# FP_connectors.net
KiCad netlist of a schematic drawn in Altium Designer
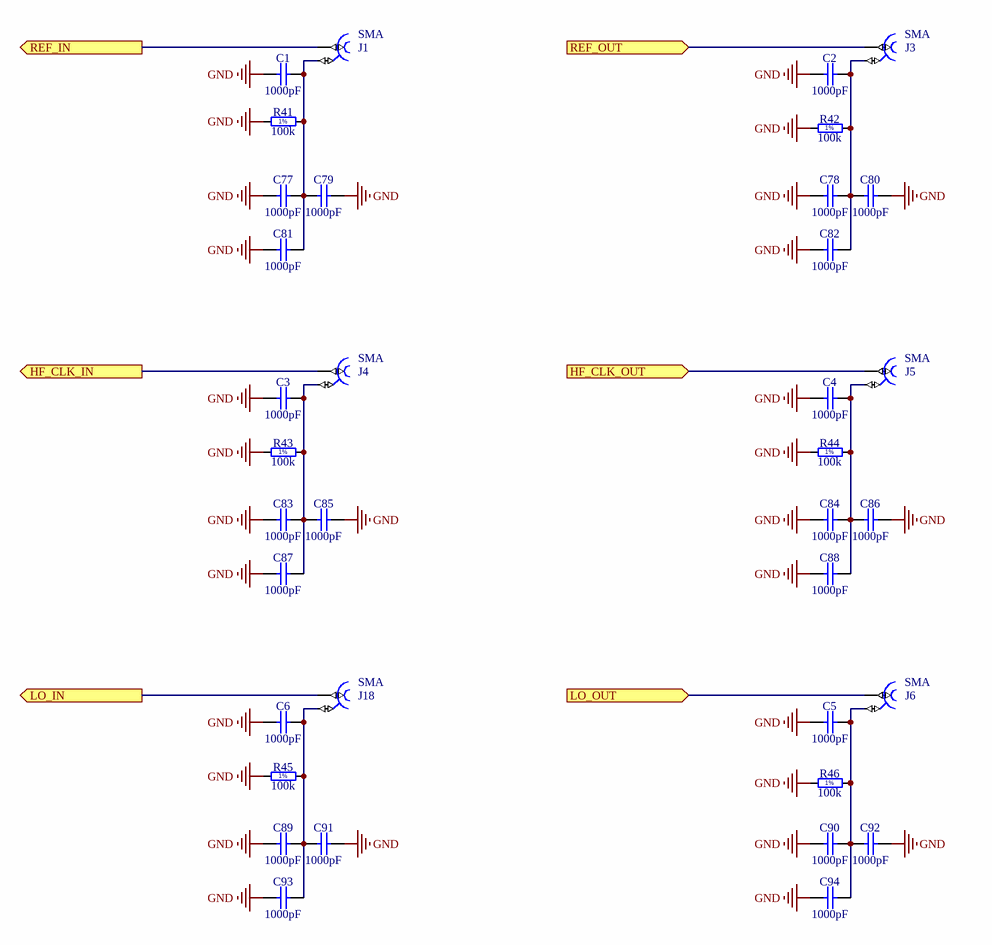
[diagram p0: FP_connectors.SchDoc]

(export (version "E")
  (design (tool "Eeschema 10.0.6"))
  (components
    (comp (ref "C1")
      (value "1000pF")
      (footprint "CAPC1005X55N")
      (description "Non-polarised capacitor")
      (fields
        (field (name "PART NUMBER") "CC0402_1000PF_50V_5%_C0G")
        (field (name "VOLTAGE") "50V")
        (field (name "AUTHOR") "CERN DEM JLC")
      )
      (libsource (lib "Capacitors") (part "Capacitor - non polarized"))
    )
    (comp (ref "C2")
      (value "1000pF")
      (footprint "CAPC1005X55N")
      (description "Non-polarised capacitor")
      (fields
        (field (name "PART NUMBER") "CC0402_1000PF_50V_5%_C0G")
        (field (name "VOLTAGE") "50V")
        (field (name "AUTHOR") "CERN DEM JLC")
      )
      (libsource (lib "Capacitors") (part "Capacitor - non polarized"))
    )
    (comp (ref "C3")
      (value "1000pF")
      (footprint "CAPC1005X55N")
      (description "Non-polarised capacitor")
      (fields
        (field (name "PART NUMBER") "CC0402_1000PF_50V_5%_C0G")
        (field (name "VOLTAGE") "50V")
        (field (name "AUTHOR") "CERN DEM JLC")
      )
      (libsource (lib "Capacitors") (part "Capacitor - non polarized"))
    )
    (comp (ref "C4")
      (value "1000pF")
      (footprint "CAPC1005X55N")
      (description "Non-polarised capacitor")
      (fields
        (field (name "PART NUMBER") "CC0402_1000PF_50V_5%_C0G")
        (field (name "VOLTAGE") "50V")
        (field (name "AUTHOR") "CERN DEM JLC")
      )
      (libsource (lib "Capacitors") (part "Capacitor - non polarized"))
    )
    (comp (ref "C5")
      (value "1000pF")
      (footprint "CAPC1005X55N")
      (description "Non-polarised capacitor")
      (fields
        (field (name "PART NUMBER") "CC0402_1000PF_50V_5%_C0G")
        (field (name "VOLTAGE") "50V")
        (field (name "AUTHOR") "CERN DEM JLC")
      )
      (libsource (lib "Capacitors") (part "Capacitor - non polarized"))
    )
    (comp (ref "C6")
      (value "1000pF")
      (footprint "CAPC1005X55N")
      (description "Non-polarised capacitor")
      (fields
        (field (name "PART NUMBER") "CC0402_1000PF_50V_5%_C0G")
        (field (name "VOLTAGE") "50V")
        (field (name "AUTHOR") "CERN DEM JLC")
      )
      (libsource (lib "Capacitors") (part "Capacitor - non polarized"))
    )
    (comp (ref "C77")
      (value "1000pF")
      (footprint "CAPC1005X55N")
      (description "Non-polarised capacitor")
      (fields
        (field (name "PART NUMBER") "CC0402_1000PF_50V_5%_C0G")
        (field (name "VOLTAGE") "50V")
        (field (name "AUTHOR") "CERN DEM JLC")
      )
      (libsource (lib "Capacitors") (part "Capacitor - non polarized"))
    )
    (comp (ref "C78")
      (value "1000pF")
      (footprint "CAPC1005X55N")
      (description "Non-polarised capacitor")
      (fields
        (field (name "PART NUMBER") "CC0402_1000PF_50V_5%_C0G")
        (field (name "VOLTAGE") "50V")
        (field (name "AUTHOR") "CERN DEM JLC")
      )
      (libsource (lib "Capacitors") (part "Capacitor - non polarized"))
    )
    (comp (ref "C79")
      (value "1000pF")
      (footprint "CAPC1005X55N")
      (description "Non-polarised capacitor")
      (fields
        (field (name "PART NUMBER") "CC0402_1000PF_50V_5%_C0G")
        (field (name "VOLTAGE") "50V")
        (field (name "AUTHOR") "CERN DEM JLC")
      )
      (libsource (lib "Capacitors") (part "Capacitor - non polarized"))
    )
    (comp (ref "C80")
      (value "1000pF")
      (footprint "CAPC1005X55N")
      (description "Non-polarised capacitor")
      (fields
        (field (name "PART NUMBER") "CC0402_1000PF_50V_5%_C0G")
        (field (name "VOLTAGE") "50V")
        (field (name "AUTHOR") "CERN DEM JLC")
      )
      (libsource (lib "Capacitors") (part "Capacitor - non polarized"))
    )
    (comp (ref "C81")
      (value "1000pF")
      (footprint "CAPC1005X55N")
      (description "Non-polarised capacitor")
      (fields
        (field (name "PART NUMBER") "CC0402_1000PF_50V_5%_C0G")
        (field (name "VOLTAGE") "50V")
        (field (name "AUTHOR") "CERN DEM JLC")
      )
      (libsource (lib "Capacitors") (part "Capacitor - non polarized"))
    )
    (comp (ref "C82")
      (value "1000pF")
      (footprint "CAPC1005X55N")
      (description "Non-polarised capacitor")
      (fields
        (field (name "PART NUMBER") "CC0402_1000PF_50V_5%_C0G")
        (field (name "VOLTAGE") "50V")
        (field (name "AUTHOR") "CERN DEM JLC")
      )
      (libsource (lib "Capacitors") (part "Capacitor - non polarized"))
    )
    (comp (ref "C83")
      (value "1000pF")
      (footprint "CAPC1005X55N")
      (description "Non-polarised capacitor")
      (fields
        (field (name "PART NUMBER") "CC0402_1000PF_50V_5%_C0G")
        (field (name "VOLTAGE") "50V")
        (field (name "AUTHOR") "CERN DEM JLC")
      )
      (libsource (lib "Capacitors") (part "Capacitor - non polarized"))
    )
    (comp (ref "C84")
      (value "1000pF")
      (footprint "CAPC1005X55N")
      (description "Non-polarised capacitor")
      (fields
        (field (name "PART NUMBER") "CC0402_1000PF_50V_5%_C0G")
        (field (name "VOLTAGE") "50V")
        (field (name "AUTHOR") "CERN DEM JLC")
      )
      (libsource (lib "Capacitors") (part "Capacitor - non polarized"))
    )
    (comp (ref "C85")
      (value "1000pF")
      (footprint "CAPC1005X55N")
      (description "Non-polarised capacitor")
      (fields
        (field (name "PART NUMBER") "CC0402_1000PF_50V_5%_C0G")
        (field (name "VOLTAGE") "50V")
        (field (name "AUTHOR") "CERN DEM JLC")
      )
      (libsource (lib "Capacitors") (part "Capacitor - non polarized"))
    )
    (comp (ref "C86")
      (value "1000pF")
      (footprint "CAPC1005X55N")
      (description "Non-polarised capacitor")
      (fields
        (field (name "PART NUMBER") "CC0402_1000PF_50V_5%_C0G")
        (field (name "VOLTAGE") "50V")
        (field (name "AUTHOR") "CERN DEM JLC")
      )
      (libsource (lib "Capacitors") (part "Capacitor - non polarized"))
    )
    (comp (ref "C87")
      (value "1000pF")
      (footprint "CAPC1005X55N")
      (description "Non-polarised capacitor")
      (fields
        (field (name "PART NUMBER") "CC0402_1000PF_50V_5%_C0G")
        (field (name "VOLTAGE") "50V")
        (field (name "AUTHOR") "CERN DEM JLC")
      )
      (libsource (lib "Capacitors") (part "Capacitor - non polarized"))
    )
    (comp (ref "C88")
      (value "1000pF")
      (footprint "CAPC1005X55N")
      (description "Non-polarised capacitor")
      (fields
        (field (name "PART NUMBER") "CC0402_1000PF_50V_5%_C0G")
        (field (name "VOLTAGE") "50V")
        (field (name "AUTHOR") "CERN DEM JLC")
      )
      (libsource (lib "Capacitors") (part "Capacitor - non polarized"))
    )
    (comp (ref "C89")
      (value "1000pF")
      (footprint "CAPC1005X55N")
      (description "Non-polarised capacitor")
      (fields
        (field (name "PART NUMBER") "CC0402_1000PF_50V_5%_C0G")
        (field (name "VOLTAGE") "50V")
        (field (name "AUTHOR") "CERN DEM JLC")
      )
      (libsource (lib "Capacitors") (part "Capacitor - non polarized"))
    )
    (comp (ref "C90")
      (value "1000pF")
      (footprint "CAPC1005X55N")
      (description "Non-polarised capacitor")
      (fields
        (field (name "PART NUMBER") "CC0402_1000PF_50V_5%_C0G")
        (field (name "VOLTAGE") "50V")
        (field (name "AUTHOR") "CERN DEM JLC")
      )
      (libsource (lib "Capacitors") (part "Capacitor - non polarized"))
    )
    (comp (ref "C91")
      (value "1000pF")
      (footprint "CAPC1005X55N")
      (description "Non-polarised capacitor")
      (fields
        (field (name "PART NUMBER") "CC0402_1000PF_50V_5%_C0G")
        (field (name "VOLTAGE") "50V")
        (field (name "AUTHOR") "CERN DEM JLC")
      )
      (libsource (lib "Capacitors") (part "Capacitor - non polarized"))
    )
    (comp (ref "C92")
      (value "1000pF")
      (footprint "CAPC1005X55N")
      (description "Non-polarised capacitor")
      (fields
        (field (name "PART NUMBER") "CC0402_1000PF_50V_5%_C0G")
        (field (name "VOLTAGE") "50V")
        (field (name "AUTHOR") "CERN DEM JLC")
      )
      (libsource (lib "Capacitors") (part "Capacitor - non polarized"))
    )
    (comp (ref "C93")
      (value "1000pF")
      (footprint "CAPC1005X55N")
      (description "Non-polarised capacitor")
      (fields
        (field (name "PART NUMBER") "CC0402_1000PF_50V_5%_C0G")
        (field (name "VOLTAGE") "50V")
        (field (name "AUTHOR") "CERN DEM JLC")
      )
      (libsource (lib "Capacitors") (part "Capacitor - non polarized"))
    )
    (comp (ref "C94")
      (value "1000pF")
      (footprint "CAPC1005X55N")
      (description "Non-polarised capacitor")
      (fields
        (field (name "PART NUMBER") "CC0402_1000PF_50V_5%_C0G")
        (field (name "VOLTAGE") "50V")
        (field (name "AUTHOR") "CERN DEM JLC")
      )
      (libsource (lib "Capacitors") (part "Capacitor - non polarized"))
    )
    (comp (ref "J1")
      (value "SMA")
      (footprint "TELEGARTNER_J01151A0451")
      (fields
        (field (name "PART NUMBER") "TELEGARTNER_J01151A0451")
        (field (name "MANUFACTURER") "TELEGARTNER")
        (field (name "MANUFACTURER PART NUMBER") "J01151A0451")
        (field (name "AUTHOR") "CERN DEM JLC")
      )
      (libsource (lib "Connectors") (part "Coax_1Female_1Shield"))
    )
    (comp (ref "J3")
      (value "SMA")
      (footprint "TELEGARTNER_J01151A0451")
      (fields
        (field (name "PART NUMBER") "TELEGARTNER_J01151A0451")
        (field (name "MANUFACTURER") "TELEGARTNER")
        (field (name "MANUFACTURER PART NUMBER") "J01151A0451")
        (field (name "AUTHOR") "CERN DEM JLC")
      )
      (libsource (lib "Connectors") (part "Coax_1Female_1Shield"))
    )
    (comp (ref "J4")
      (value "SMA")
      (footprint "TELEGARTNER_J01151A0451")
      (fields
        (field (name "PART NUMBER") "TELEGARTNER_J01151A0451")
        (field (name "MANUFACTURER") "TELEGARTNER")
        (field (name "MANUFACTURER PART NUMBER") "J01151A0451")
        (field (name "AUTHOR") "CERN DEM JLC")
      )
      (libsource (lib "Connectors") (part "Coax_1Female_1Shield"))
    )
    (comp (ref "J5")
      (value "SMA")
      (footprint "TELEGARTNER_J01151A0451")
      (fields
        (field (name "PART NUMBER") "TELEGARTNER_J01151A0451")
        (field (name "MANUFACTURER") "TELEGARTNER")
        (field (name "MANUFACTURER PART NUMBER") "J01151A0451")
        (field (name "AUTHOR") "CERN DEM JLC")
      )
      (libsource (lib "Connectors") (part "Coax_1Female_1Shield"))
    )
    (comp (ref "J6")
      (value "SMA")
      (footprint "TELEGARTNER_J01151A0451")
      (fields
        (field (name "PART NUMBER") "TELEGARTNER_J01151A0451")
        (field (name "MANUFACTURER") "TELEGARTNER")
        (field (name "MANUFACTURER PART NUMBER") "J01151A0451")
        (field (name "AUTHOR") "CERN DEM JLC")
      )
      (libsource (lib "Connectors") (part "Coax_1Female_1Shield"))
    )
    (comp (ref "J18")
      (value "SMA")
      (footprint "TELEGARTNER_J01151A0451")
      (fields
        (field (name "PART NUMBER") "TELEGARTNER_J01151A0451")
        (field (name "MANUFACTURER") "TELEGARTNER")
        (field (name "MANUFACTURER PART NUMBER") "J01151A0451")
        (field (name "AUTHOR") "CERN DEM JLC")
      )
      (libsource (lib "Connectors") (part "Coax_1Female_1Shield"))
    )
    (comp (ref "R41")
      (value "100k")
      (footprint "RESC1005X40N")
      (description "Resistor - 1%")
      (fields
        (field (name "PART NUMBER") "R0402_100k_1%_0.0625W_100PPM")
        (field (name "POWER") "0.0625W")
        (field (name "AUTHOR") "CERN DEM JLC")
      )
      (libsource (lib "Resistors") (part "Resistor - 1%"))
    )
    (comp (ref "R42")
      (value "100k")
      (footprint "RESC1005X40N")
      (description "Resistor - 1%")
      (fields
        (field (name "PART NUMBER") "R0402_100k_1%_0.0625W_100PPM")
        (field (name "POWER") "0.0625W")
        (field (name "AUTHOR") "CERN DEM JLC")
      )
      (libsource (lib "Resistors") (part "Resistor - 1%"))
    )
    (comp (ref "R43")
      (value "100k")
      (footprint "RESC1005X40N")
      (description "Resistor - 1%")
      (fields
        (field (name "PART NUMBER") "R0402_100k_1%_0.0625W_100PPM")
        (field (name "POWER") "0.0625W")
        (field (name "AUTHOR") "CERN DEM JLC")
      )
      (libsource (lib "Resistors") (part "Resistor - 1%"))
    )
    (comp (ref "R44")
      (value "100k")
      (footprint "RESC1005X40N")
      (description "Resistor - 1%")
      (fields
        (field (name "PART NUMBER") "R0402_100k_1%_0.0625W_100PPM")
        (field (name "POWER") "0.0625W")
        (field (name "AUTHOR") "CERN DEM JLC")
      )
      (libsource (lib "Resistors") (part "Resistor - 1%"))
    )
    (comp (ref "R45")
      (value "100k")
      (footprint "RESC1005X40N")
      (description "Resistor - 1%")
      (fields
        (field (name "PART NUMBER") "R0402_100k_1%_0.0625W_100PPM")
        (field (name "POWER") "0.0625W")
        (field (name "AUTHOR") "CERN DEM JLC")
      )
      (libsource (lib "Resistors") (part "Resistor - 1%"))
    )
    (comp (ref "R46")
      (value "100k")
      (footprint "RESC1005X40N")
      (description "Resistor - 1%")
      (fields
        (field (name "PART NUMBER") "R0402_100k_1%_0.0625W_100PPM")
        (field (name "POWER") "0.0625W")
        (field (name "AUTHOR") "CERN DEM JLC")
      )
      (libsource (lib "Resistors") (part "Resistor - 1%"))
    )
  )
  (nets
    (net (code "1") (name "/HF_CLK_IN") (class "Default")
      (node (ref "J4") (pin "1") (pinfunction "1_1") (pintype "bidirectional"))
    )
    (net (code "2") (name "/HF_CLK_OUT") (class "Default")
      (node (ref "J5") (pin "1") (pinfunction "1_1") (pintype "bidirectional"))
    )
    (net (code "3") (name "/LO_IN") (class "Default")
      (node (ref "J18") (pin "1") (pinfunction "1_1") (pintype "bidirectional"))
    )
    (net (code "4") (name "/LO_OUT") (class "Default")
      (node (ref "J6") (pin "1") (pinfunction "1_1") (pintype "bidirectional"))
    )
    (net (code "5") (name "/REF_IN") (class "Default")
      (node (ref "J1") (pin "1") (pinfunction "1_1") (pintype "bidirectional"))
    )
    (net (code "6") (name "/REF_OUT") (class "Default")
      (node (ref "J3") (pin "1") (pinfunction "1_1") (pintype "bidirectional"))
    )
    (net (code "7") (name "GND") (class "Default")
      (node (ref "C1") (pin "1") (pinfunction "1_1") (pintype "passive"))
      (node (ref "C2") (pin "1") (pinfunction "1_1") (pintype "passive"))
      (node (ref "C3") (pin "1") (pinfunction "1_1") (pintype "passive"))
      (node (ref "C4") (pin "1") (pinfunction "1_1") (pintype "passive"))
      (node (ref "C5") (pin "1") (pinfunction "1_1") (pintype "passive"))
      (node (ref "C6") (pin "1") (pinfunction "1_1") (pintype "passive"))
      (node (ref "C77") (pin "1") (pinfunction "1_1") (pintype "passive"))
      (node (ref "C78") (pin "1") (pinfunction "1_1") (pintype "passive"))
      (node (ref "C79") (pin "2") (pinfunction "2_2") (pintype "passive"))
      (node (ref "C80") (pin "2") (pinfunction "2_2") (pintype "passive"))
      (node (ref "C81") (pin "1") (pinfunction "1_1") (pintype "passive"))
      (node (ref "C82") (pin "1") (pinfunction "1_1") (pintype "passive"))
      (node (ref "C83") (pin "1") (pinfunction "1_1") (pintype "passive"))
      (node (ref "C84") (pin "1") (pinfunction "1_1") (pintype "passive"))
      (node (ref "C85") (pin "2") (pinfunction "2_2") (pintype "passive"))
      (node (ref "C86") (pin "2") (pinfunction "2_2") (pintype "passive"))
      (node (ref "C87") (pin "1") (pinfunction "1_1") (pintype "passive"))
      (node (ref "C88") (pin "1") (pinfunction "1_1") (pintype "passive"))
      (node (ref "C89") (pin "1") (pinfunction "1_1") (pintype "passive"))
      (node (ref "C90") (pin "1") (pinfunction "1_1") (pintype "passive"))
      (node (ref "C91") (pin "2") (pinfunction "2_2") (pintype "passive"))
      (node (ref "C92") (pin "2") (pinfunction "2_2") (pintype "passive"))
      (node (ref "C93") (pin "1") (pinfunction "1_1") (pintype "passive"))
      (node (ref "C94") (pin "1") (pinfunction "1_1") (pintype "passive"))
      (node (ref "R41") (pin "1") (pinfunction "1_1") (pintype "passive"))
      (node (ref "R42") (pin "1") (pinfunction "1_1") (pintype "passive"))
      (node (ref "R43") (pin "1") (pinfunction "1_1") (pintype "passive"))
      (node (ref "R44") (pin "1") (pinfunction "1_1") (pintype "passive"))
      (node (ref "R45") (pin "1") (pinfunction "1_1") (pintype "passive"))
      (node (ref "R46") (pin "1") (pinfunction "1_1") (pintype "passive"))
    )
    (net (code "8") (name "Net-(C1-Pad2)") (class "Default")
      (node (ref "C1") (pin "2") (pinfunction "2_2") (pintype "passive"))
      (node (ref "C77") (pin "2") (pinfunction "2_2") (pintype "passive"))
      (node (ref "C79") (pin "1") (pinfunction "1_1") (pintype "passive"))
      (node (ref "C81") (pin "2") (pinfunction "2_2") (pintype "passive"))
      (node (ref "J1") (pin "2") (pinfunction "2_2") (pintype "bidirectional"))
      (node (ref "R41") (pin "2") (pinfunction "2_2") (pintype "passive"))
    )
    (net (code "9") (name "Net-(C2-Pad2)") (class "Default")
      (node (ref "C2") (pin "2") (pinfunction "2_2") (pintype "passive"))
      (node (ref "C78") (pin "2") (pinfunction "2_2") (pintype "passive"))
      (node (ref "C80") (pin "1") (pinfunction "1_1") (pintype "passive"))
      (node (ref "C82") (pin "2") (pinfunction "2_2") (pintype "passive"))
      (node (ref "J3") (pin "2") (pinfunction "2_2") (pintype "bidirectional"))
      (node (ref "R42") (pin "2") (pinfunction "2_2") (pintype "passive"))
    )
    (net (code "10") (name "Net-(C3-Pad2)") (class "Default")
      (node (ref "C3") (pin "2") (pinfunction "2_2") (pintype "passive"))
      (node (ref "C83") (pin "2") (pinfunction "2_2") (pintype "passive"))
      (node (ref "C85") (pin "1") (pinfunction "1_1") (pintype "passive"))
      (node (ref "C87") (pin "2") (pinfunction "2_2") (pintype "passive"))
      (node (ref "J4") (pin "2") (pinfunction "2_2") (pintype "bidirectional"))
      (node (ref "R43") (pin "2") (pinfunction "2_2") (pintype "passive"))
    )
    (net (code "11") (name "Net-(C4-Pad2)") (class "Default")
      (node (ref "C4") (pin "2") (pinfunction "2_2") (pintype "passive"))
      (node (ref "C84") (pin "2") (pinfunction "2_2") (pintype "passive"))
      (node (ref "C86") (pin "1") (pinfunction "1_1") (pintype "passive"))
      (node (ref "C88") (pin "2") (pinfunction "2_2") (pintype "passive"))
      (node (ref "J5") (pin "2") (pinfunction "2_2") (pintype "bidirectional"))
      (node (ref "R44") (pin "2") (pinfunction "2_2") (pintype "passive"))
    )
    (net (code "12") (name "Net-(C5-Pad2)") (class "Default")
      (node (ref "C5") (pin "2") (pinfunction "2_2") (pintype "passive"))
      (node (ref "C90") (pin "2") (pinfunction "2_2") (pintype "passive"))
      (node (ref "C92") (pin "1") (pinfunction "1_1") (pintype "passive"))
      (node (ref "C94") (pin "2") (pinfunction "2_2") (pintype "passive"))
      (node (ref "J6") (pin "2") (pinfunction "2_2") (pintype "bidirectional"))
      (node (ref "R46") (pin "2") (pinfunction "2_2") (pintype "passive"))
    )
    (net (code "13") (name "Net-(C6-Pad2)") (class "Default")
      (node (ref "C6") (pin "2") (pinfunction "2_2") (pintype "passive"))
      (node (ref "C89") (pin "2") (pinfunction "2_2") (pintype "passive"))
      (node (ref "C91") (pin "1") (pinfunction "1_1") (pintype "passive"))
      (node (ref "C93") (pin "2") (pinfunction "2_2") (pintype "passive"))
      (node (ref "J18") (pin "2") (pinfunction "2_2") (pintype "bidirectional"))
      (node (ref "R45") (pin "2") (pinfunction "2_2") (pintype "passive"))
    )
  )
)
